# Neutrino-150.net
KiCad netlist of a schematic drawn in EAGLE
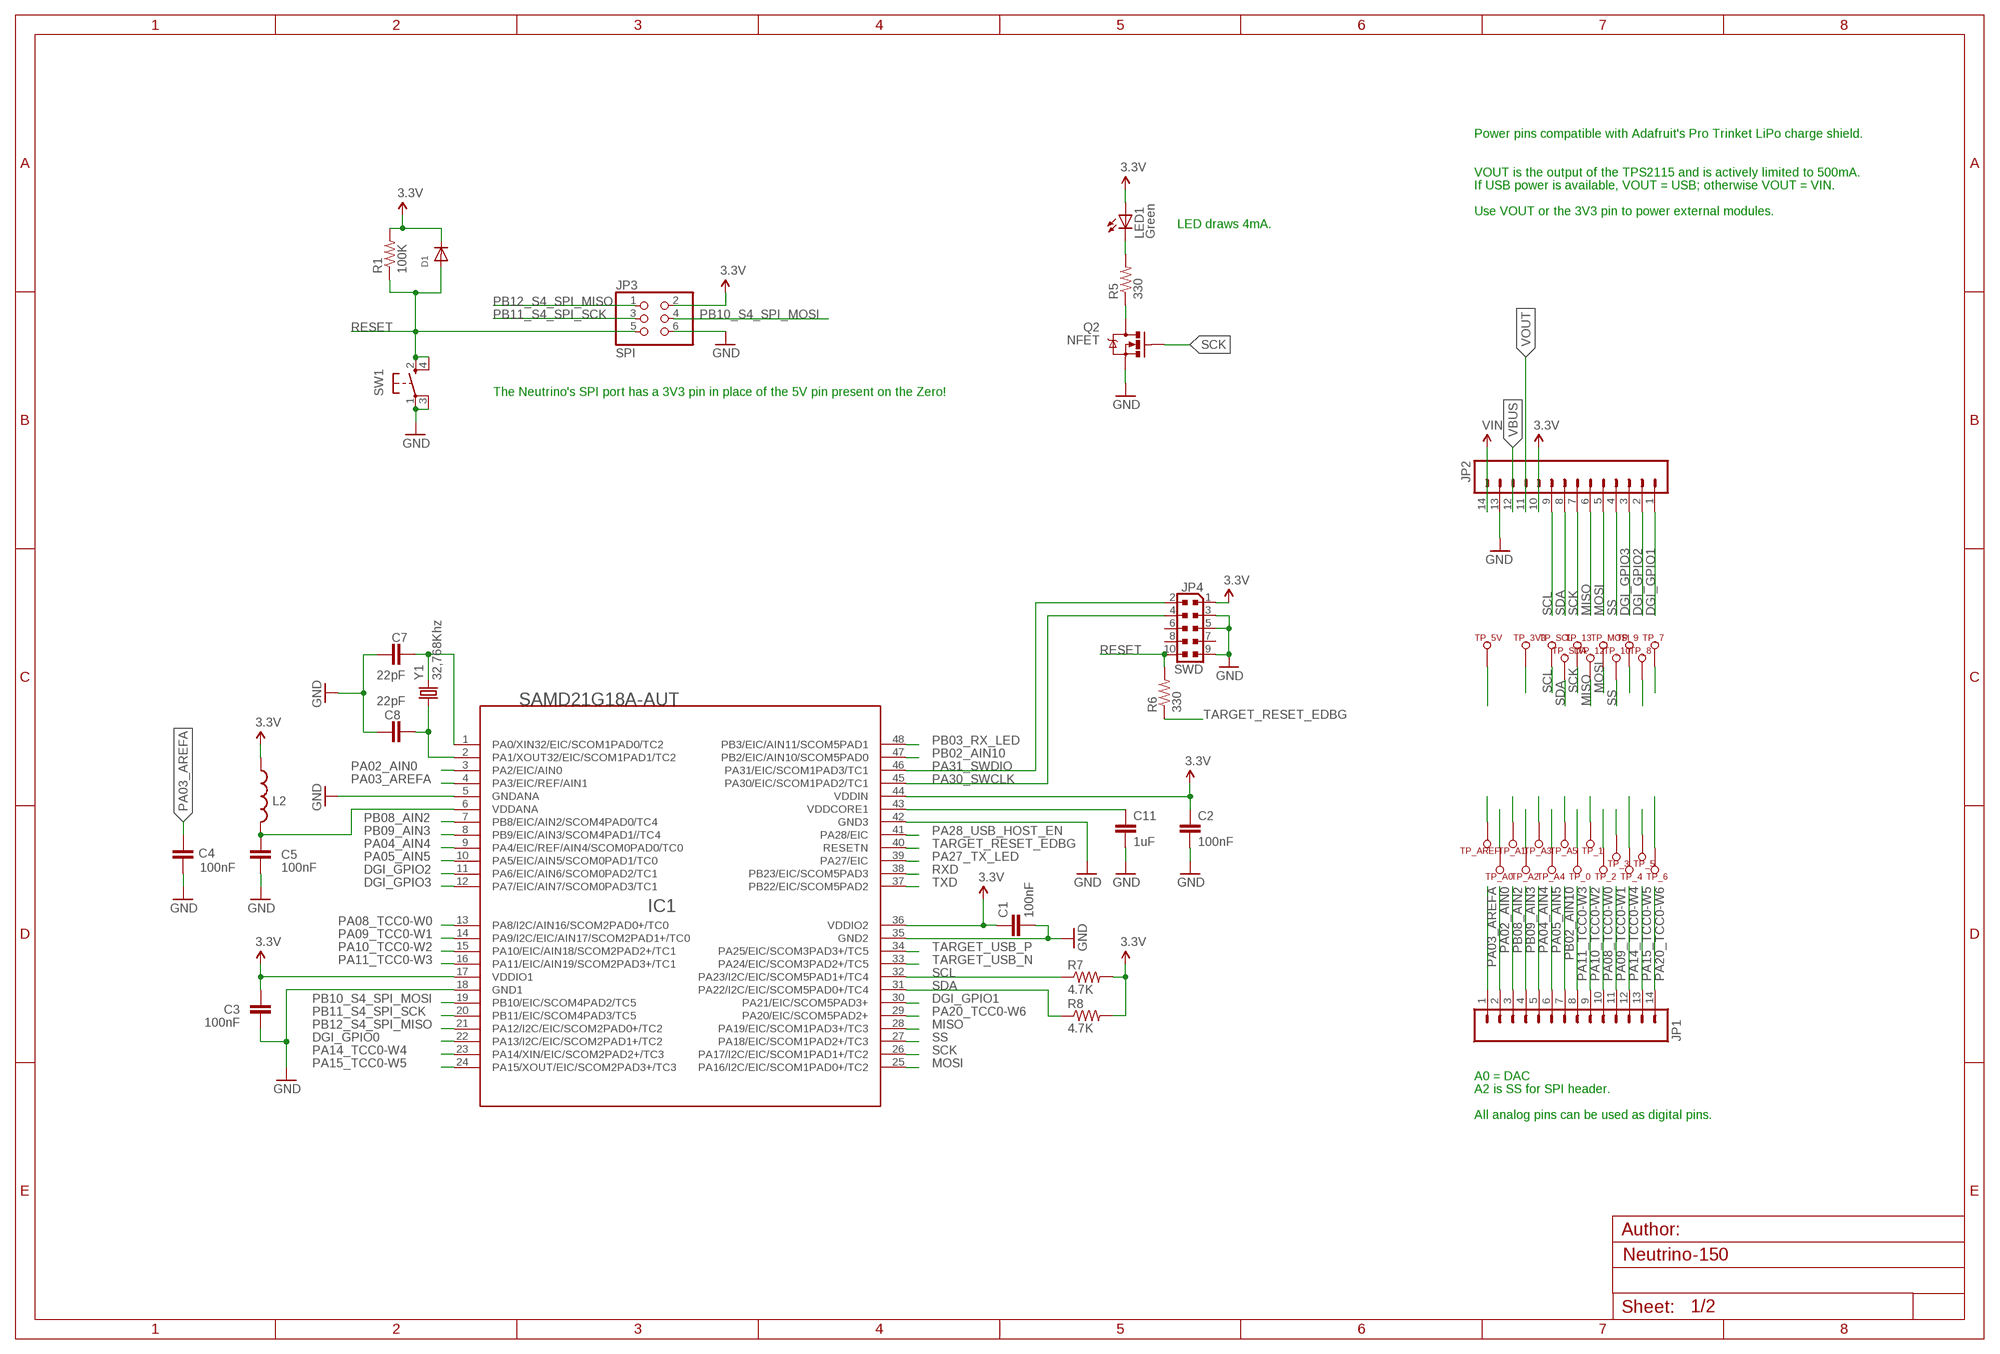
[diagram p0: schematic, sheet 1]
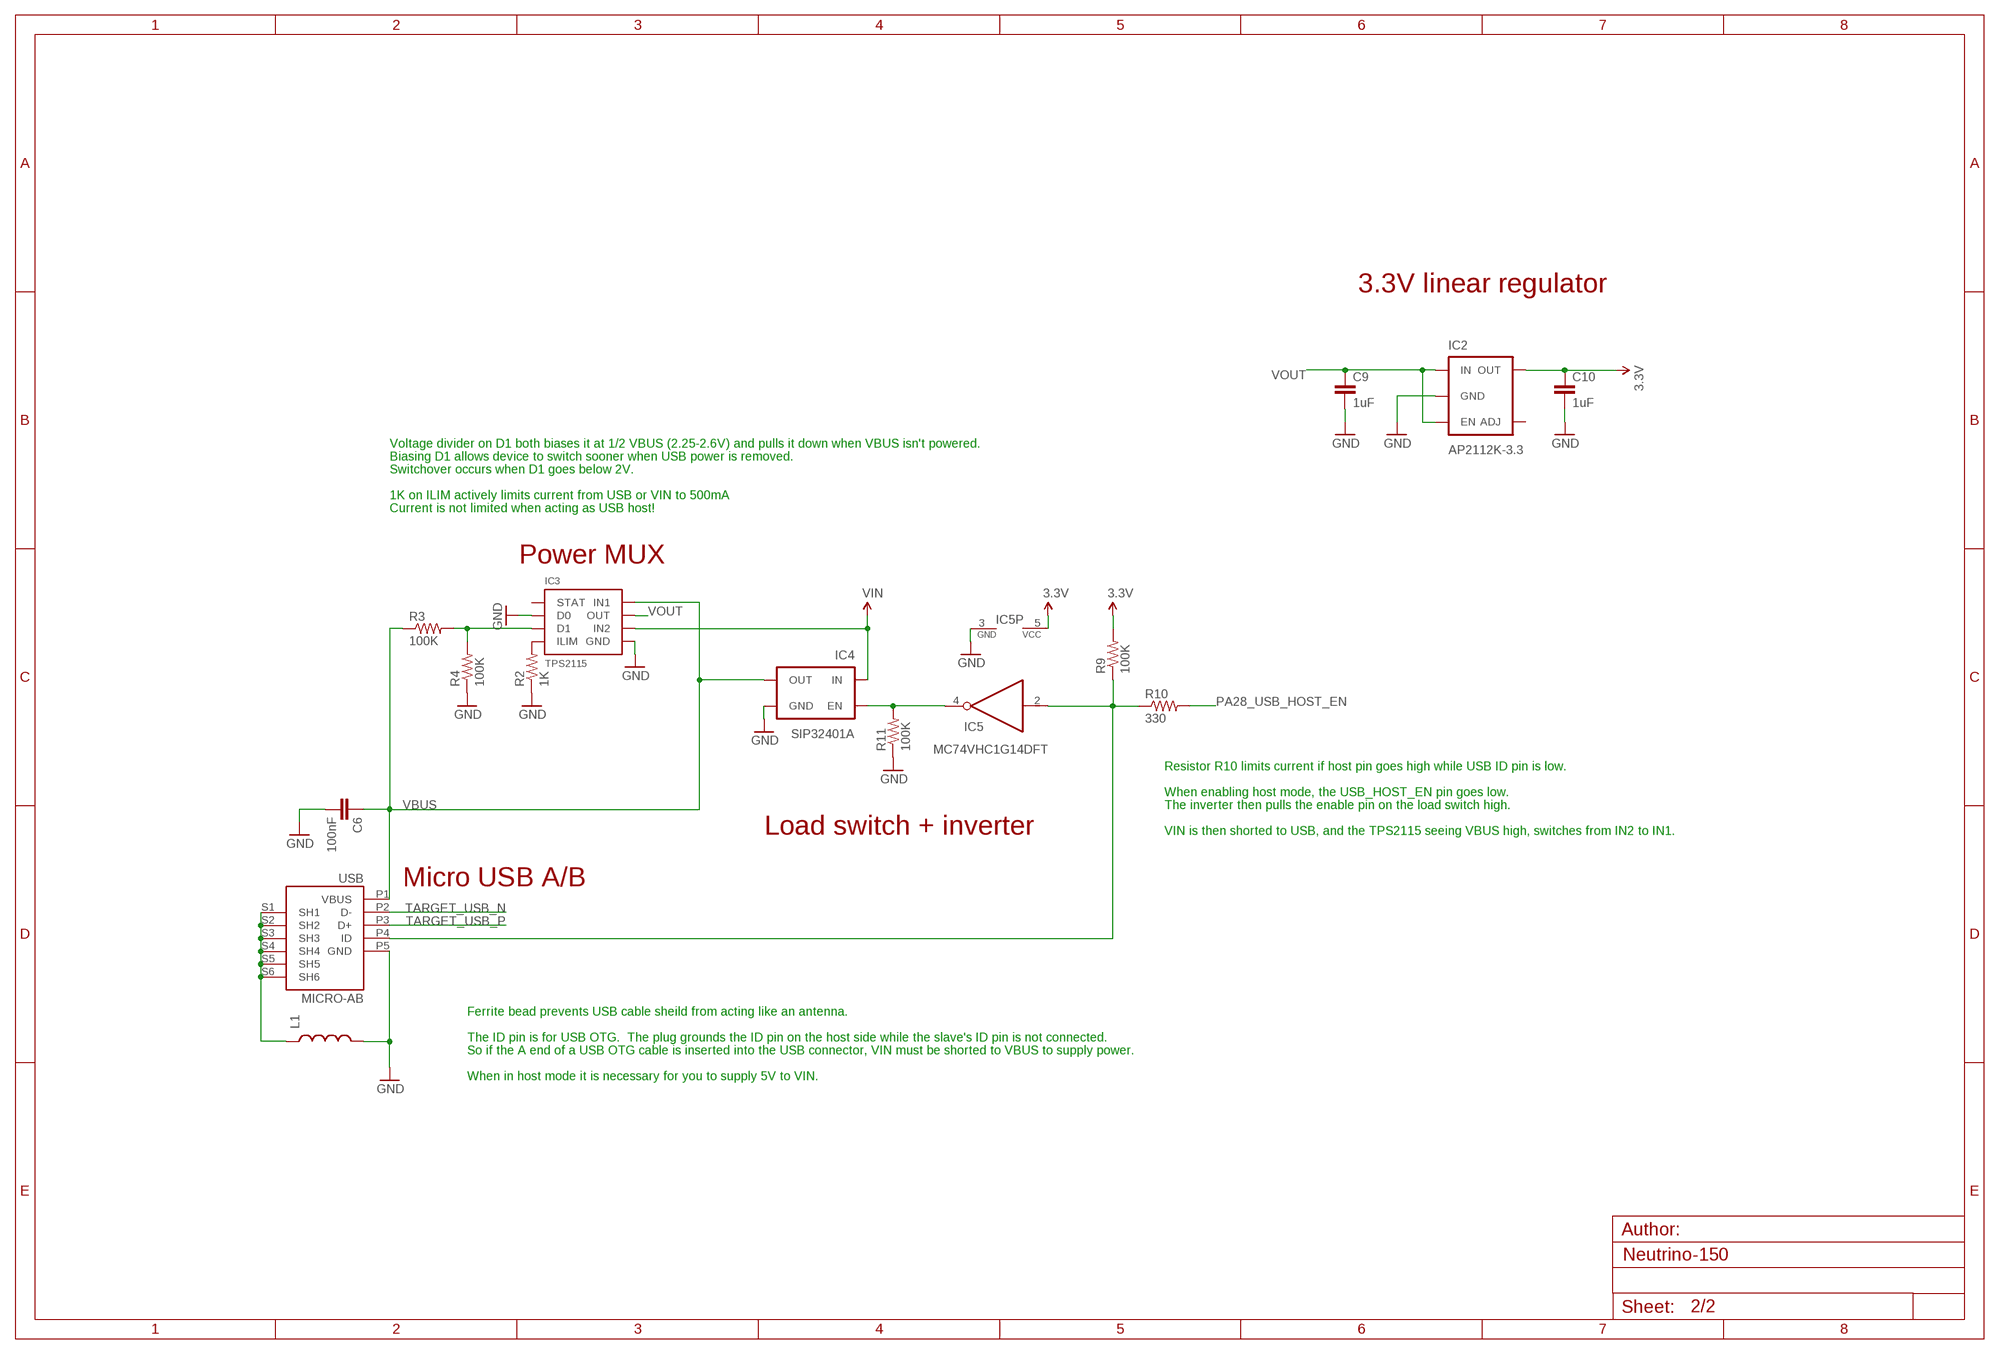
[diagram p1: schematic, sheet 2]

(export (version "E")
  (design (tool "Eeschema 10.0.6"))
  (components
    (comp (ref "C6")
      (value "100nF")
      (footprint "eagle-import:0402-CAP")
      (libsource (lib "eagle-import") (part "CAP0402"))
    )
    (comp (ref "C9")
      (value "1uF")
      (footprint "eagle-import:0402-CAP")
      (libsource (lib "eagle-import") (part "CAP0402"))
    )
    (comp (ref "C10")
      (value "1uF")
      (footprint "eagle-import:0402-CAP")
      (libsource (lib "eagle-import") (part "CAP0402"))
    )
    (comp (ref "IC2")
      (value "AP2112K-3.3")
      (footprint "eagle-import:SOT23-5")
      (libsource (lib "eagle-import") (part "AP2202-ADJ"))
    )
    (comp (ref "IC3")
      (value "TPS2115")
      (footprint "eagle-import:8-VDFN")
      (libsource (lib "eagle-import") (part "TPS2115"))
    )
    (comp (ref "IC4")
      (value "SIP32401A")
      (footprint "eagle-import:TDFN4")
      (libsource (lib "eagle-import") (part "SIP32401A"))
    )
    (comp (ref "IC5")
      (value "MC74VHC1G14DFT")
      (footprint "eagle-import:SC70-5")
      (libsource (lib "eagle-import") (part "741G04DCKAHC"))
    )
    (comp (ref "L1")
      (value "INDUCTOR0603-TDK")
      (footprint "eagle-import:0603-TDK")
      (libsource (lib "eagle-import") (part "INDUCTOR0603-TDK"))
    )
    (comp (ref "R2")
      (value "1K")
      (footprint "eagle-import:R0402-VISHAY")
      (libsource (lib "eagle-import") (part "R-US_R0402-VISHAY"))
    )
    (comp (ref "R3")
      (value "100K")
      (footprint "eagle-import:R0402-VISHAY")
      (libsource (lib "eagle-import") (part "R-US_R0402-VISHAY"))
    )
    (comp (ref "R4")
      (value "100K")
      (footprint "eagle-import:R0402-VISHAY")
      (libsource (lib "eagle-import") (part "R-US_R0402-VISHAY"))
    )
    (comp (ref "R9")
      (value "100K")
      (footprint "eagle-import:R0402-VISHAY")
      (libsource (lib "eagle-import") (part "R-US_R0402-VISHAY"))
    )
    (comp (ref "R10")
      (value "330")
      (footprint "eagle-import:R0402-VISHAY")
      (libsource (lib "eagle-import") (part "R-US_R0402-VISHAY"))
    )
    (comp (ref "R11")
      (value "100K")
      (footprint "eagle-import:R0402-VISHAY")
      (libsource (lib "eagle-import") (part "R-US_R0402-VISHAY"))
    )
    (comp (ref "USB")
      (value "MICRO-AB")
      (footprint "eagle-import:MOLEX_USB_MICRO_AB")
      (libsource (lib "eagle-import") (part "MOLEX_USB_MICRO_AB"))
    )
    (comp (ref "C1")
      (value "100nF")
      (footprint "eagle-import:0402-CAP")
      (libsource (lib "eagle-import") (part "CAP0402"))
    )
    (comp (ref "C2")
      (value "100nF")
      (footprint "eagle-import:0402-CAP")
      (libsource (lib "eagle-import") (part "CAP0402"))
    )
    (comp (ref "C3")
      (value "100nF")
      (footprint "eagle-import:0402-CAP")
      (libsource (lib "eagle-import") (part "CAP0402"))
    )
    (comp (ref "C4")
      (value "100nF")
      (footprint "eagle-import:0402-CAP")
      (libsource (lib "eagle-import") (part "CAP0402"))
    )
    (comp (ref "C5")
      (value "100nF")
      (footprint "eagle-import:0402-CAP")
      (libsource (lib "eagle-import") (part "CAP0402"))
    )
    (comp (ref "C7")
      (value "22pF")
      (footprint "eagle-import:0402-CAP")
      (libsource (lib "eagle-import") (part "CAP0402"))
    )
    (comp (ref "C8")
      (value "22pF")
      (footprint "eagle-import:0402-CAP")
      (libsource (lib "eagle-import") (part "CAP0402"))
    )
    (comp (ref "C11")
      (value "1uF")
      (footprint "eagle-import:0402-CAP")
      (libsource (lib "eagle-import") (part "CAP0402"))
    )
    (comp (ref "D1")
      (value "DIODESOD-523")
      (footprint "eagle-import:SOD-523")
      (libsource (lib "eagle-import") (part "DIODESOD-523"))
    )
    (comp (ref "IC1")
      (value "SAMD21G18A-AUT")
      (footprint "eagle-import:INTEGRATEDCIRCUITS_TQFP48-7X7")
      (libsource (lib "eagle-import") (part "INTEGRATEDCIRCUITS_1792_SAMD21G18A-AUT"))
    )
    (comp (ref "JP1")
      (value "M14NOSILK_SMALLPADS")
      (footprint "eagle-import:1X14_NO_SILK_SMALLPADS")
      (libsource (lib "eagle-import") (part "M14NOSILK_SMALLPADS"))
    )
    (comp (ref "JP2")
      (value "M14NOSILK_SMALLPADS")
      (footprint "eagle-import:1X14_NO_SILK_SMALLPADS")
      (libsource (lib "eagle-import") (part "M14NOSILK_SMALLPADS"))
    )
    (comp (ref "JP3")
      (value "SPI")
      (footprint "eagle-import:CONNETTORI_2X03")
      (fields (field (name "PART_NUMBER") "PH254-203DF118A00V"))
      (libsource (lib "eagle-import") (part "CONNETTORI_0114_PH254-203DF118A00V"))
    )
    (comp (ref "JP4")
      (value "SWD")
      (footprint "eagle-import:CONNETTORI_PINHEAD-2X5-P127")
      (libsource (lib "eagle-import") (part "CONNETTORI_0171_PH127-205DF055G00A"))
    )
    (comp (ref "L2")
      (value "INDUCTOR0603-TDK")
      (footprint "eagle-import:0603-TDK")
      (libsource (lib "eagle-import") (part "INDUCTOR0603-TDK"))
    )
    (comp (ref "LED1")
      (value "Green")
      (footprint "eagle-import:CHIPLED_0805")
      (fields (field (name "PART_NUMBER") "KPT-2012YC"))
      (libsource (lib "eagle-import") (part "0044_KPT-2012YC"))
    )
    (comp (ref "Q2")
      (value "NFET")
      (footprint "eagle-import:SOT323")
      (libsource (lib "eagle-import") (part "MOSFET-NCHANNEL2N7002PW"))
    )
    (comp (ref "R1")
      (value "100K")
      (footprint "eagle-import:R0402-VISHAY")
      (libsource (lib "eagle-import") (part "R-US_R0402-VISHAY"))
    )
    (comp (ref "R5")
      (value "330")
      (footprint "eagle-import:R0402-VISHAY")
      (libsource (lib "eagle-import") (part "R-US_R0402-VISHAY"))
    )
    (comp (ref "R6")
      (value "330")
      (footprint "eagle-import:R0402-VISHAY")
      (libsource (lib "eagle-import") (part "R-US_R0402-VISHAY"))
    )
    (comp (ref "R7")
      (value "4.7K")
      (footprint "eagle-import:R0402-VISHAY")
      (libsource (lib "eagle-import") (part "R-US_R0402-VISHAY"))
    )
    (comp (ref "R8")
      (value "4.7K")
      (footprint "eagle-import:R0402-VISHAY")
      (libsource (lib "eagle-import") (part "R-US_R0402-VISHAY"))
    )
    (comp (ref "SW1")
      (value "SPST_TACT-KMR2")
      (footprint "eagle-import:KMR2")
      (libsource (lib "eagle-import") (part "SPST_TACT-KMR2"))
    )
    (comp (ref "TP_0")
      (value "TP_SP")
      (footprint "eagle-import:TP-SP")
      (libsource (lib "eagle-import") (part "TP_SP"))
    )
    (comp (ref "TP_1")
      (value "TP_SP")
      (footprint "eagle-import:TP-SP")
      (libsource (lib "eagle-import") (part "TP_SP"))
    )
    (comp (ref "TP_2")
      (value "TP_SP")
      (footprint "eagle-import:TP-SP")
      (libsource (lib "eagle-import") (part "TP_SP"))
    )
    (comp (ref "TP_3")
      (value "TP_SP")
      (footprint "eagle-import:TP-SP")
      (libsource (lib "eagle-import") (part "TP_SP"))
    )
    (comp (ref "TP_3V3")
      (value "TP_SP")
      (footprint "eagle-import:TP-SP")
      (libsource (lib "eagle-import") (part "TP_SP"))
    )
    (comp (ref "TP_4")
      (value "TP_SP")
      (footprint "eagle-import:TP-SP")
      (libsource (lib "eagle-import") (part "TP_SP"))
    )
    (comp (ref "TP_5")
      (value "TP_SP")
      (footprint "eagle-import:TP-SP")
      (libsource (lib "eagle-import") (part "TP_SP"))
    )
    (comp (ref "TP_5V")
      (value "TP_SP")
      (footprint "eagle-import:TP-SP")
      (libsource (lib "eagle-import") (part "TP_SP"))
    )
    (comp (ref "TP_6")
      (value "TP_SP")
      (footprint "eagle-import:TP-SP")
      (libsource (lib "eagle-import") (part "TP_SP"))
    )
    (comp (ref "TP_7")
      (value "TP_SP")
      (footprint "eagle-import:TP-SP")
      (libsource (lib "eagle-import") (part "TP_SP"))
    )
    (comp (ref "TP_8")
      (value "TP_SP")
      (footprint "eagle-import:TP-SP")
      (libsource (lib "eagle-import") (part "TP_SP"))
    )
    (comp (ref "TP_9")
      (value "TP_SP")
      (footprint "eagle-import:TP-SP")
      (libsource (lib "eagle-import") (part "TP_SP"))
    )
    (comp (ref "TP_10")
      (value "TP_SP")
      (footprint "eagle-import:TP-SP")
      (libsource (lib "eagle-import") (part "TP_SP"))
    )
    (comp (ref "TP_12")
      (value "TP_SP")
      (footprint "eagle-import:TP-SP")
      (libsource (lib "eagle-import") (part "TP_SP"))
    )
    (comp (ref "TP_13")
      (value "TP_SP")
      (footprint "eagle-import:TP-SP")
      (libsource (lib "eagle-import") (part "TP_SP"))
    )
    (comp (ref "TP_A0")
      (value "TP_SP")
      (footprint "eagle-import:TP-SP")
      (libsource (lib "eagle-import") (part "TP_SP"))
    )
    (comp (ref "TP_A1")
      (value "TP_SP")
      (footprint "eagle-import:TP-SP")
      (libsource (lib "eagle-import") (part "TP_SP"))
    )
    (comp (ref "TP_A2")
      (value "TP_SP")
      (footprint "eagle-import:TP-SP")
      (libsource (lib "eagle-import") (part "TP_SP"))
    )
    (comp (ref "TP_A3")
      (value "TP_SP")
      (footprint "eagle-import:TP-SP")
      (libsource (lib "eagle-import") (part "TP_SP"))
    )
    (comp (ref "TP_A4")
      (value "TP_SP")
      (footprint "eagle-import:TP-SP")
      (libsource (lib "eagle-import") (part "TP_SP"))
    )
    (comp (ref "TP_A5")
      (value "TP_SP")
      (footprint "eagle-import:TP-SP")
      (libsource (lib "eagle-import") (part "TP_SP"))
    )
    (comp (ref "TP_AREF")
      (value "TP_SP")
      (footprint "eagle-import:TP-SP")
      (libsource (lib "eagle-import") (part "TP_SP"))
    )
    (comp (ref "TP_MOSI")
      (value "TP_SP")
      (footprint "eagle-import:TP-SP")
      (libsource (lib "eagle-import") (part "TP_SP"))
    )
    (comp (ref "TP_SCL")
      (value "TP_SP")
      (footprint "eagle-import:TP-SP")
      (libsource (lib "eagle-import") (part "TP_SP"))
    )
    (comp (ref "TP_SDA")
      (value "TP_SP")
      (footprint "eagle-import:TP-SP")
      (libsource (lib "eagle-import") (part "TP_SP"))
    )
    (comp (ref "Y1")
      (value "32,768Khz")
      (footprint "eagle-import:CRYSTAL-SMD-2.0X1.2")
      (libsource (lib "eagle-import") (part "CRYSTAL2012"))
    )
  )
  (nets
    (net (code "1") (name "3.3V") (class "Default")
      (node (ref "C1") (pin "1") (pinfunction "1_1") (pintype "passive"))
      (node (ref "C10") (pin "1") (pinfunction "1_1") (pintype "passive"))
      (node (ref "C2") (pin "1") (pinfunction "1_1") (pintype "passive"))
      (node (ref "C3") (pin "2") (pinfunction "2_2") (pintype "passive"))
      (node (ref "D1") (pin "K") (pinfunction "C_K") (pintype "passive"))
      (node (ref "IC1") (pin "17") (pinfunction "VDDIO1_17") (pintype "power_in"))
      (node (ref "IC1") (pin "36") (pinfunction "VDDIO2_36") (pintype "power_in"))
      (node (ref "IC1") (pin "44") (pinfunction "VDDIN_44") (pintype "power_in"))
      (node (ref "IC2") (pin "5") (pinfunction "OUT_5") (pintype "passive"))
      (node (ref "IC5") (pin "5") (pinfunction "VCC_5") (pintype "power_in"))
      (node (ref "JP2") (pin "10") (pinfunction "10_10") (pintype "passive"))
      (node (ref "JP3") (pin "2") (pinfunction "2_2") (pintype "passive"))
      (node (ref "JP4") (pin "1") (pinfunction "1_1") (pintype "passive"))
      (node (ref "L2") (pin "1") (pinfunction "1_1") (pintype "passive"))
      (node (ref "LED1") (pin "A") (pinfunction "A_A") (pintype "passive"))
      (node (ref "R1") (pin "2") (pinfunction "2_2") (pintype "passive"))
      (node (ref "R7") (pin "2") (pinfunction "2_2") (pintype "passive"))
      (node (ref "R8") (pin "2") (pinfunction "2_2") (pintype "passive"))
      (node (ref "R9") (pin "2") (pinfunction "2_2") (pintype "passive"))
      (node (ref "TP_3V3") (pin "X") (pinfunction "TESTP_X") (pintype "passive"))
    )
    (net (code "2") (name "DGI_GPIO0") (class "Default")
      (node (ref "IC1") (pin "22") (pinfunction "PA13/I2C/EIC/SCOM2PAD1+/TC2_22") (pintype "bidirectional"))
    )
    (net (code "3") (name "DGI_GPIO1") (class "Default")
      (node (ref "IC1") (pin "30") (pinfunction "PA21/EIC/SCOM5PAD3+_30") (pintype "bidirectional"))
      (node (ref "JP2") (pin "1") (pinfunction "1_1") (pintype "passive"))
      (node (ref "TP_7") (pin "X") (pinfunction "TESTP_X") (pintype "passive"))
    )
    (net (code "4") (name "DGI_GPIO2") (class "Default")
      (node (ref "IC1") (pin "11") (pinfunction "PA6/EIC/AIN6/SCOM0PAD2/TC1_11") (pintype "bidirectional"))
      (node (ref "JP2") (pin "2") (pinfunction "2_2") (pintype "passive"))
      (node (ref "TP_8") (pin "X") (pinfunction "TESTP_X") (pintype "passive"))
    )
    (net (code "5") (name "DGI_GPIO3") (class "Default")
      (node (ref "IC1") (pin "12") (pinfunction "PA7/EIC/AIN7/SCOM0PAD3/TC1_12") (pintype "bidirectional"))
      (node (ref "JP2") (pin "3") (pinfunction "3_3") (pintype "passive"))
      (node (ref "TP_9") (pin "X") (pinfunction "TESTP_X") (pintype "passive"))
    )
    (net (code "6") (name "GND") (class "Default")
      (node (ref "C1") (pin "2") (pinfunction "2_2") (pintype "passive"))
      (node (ref "C10") (pin "2") (pinfunction "2_2") (pintype "passive"))
      (node (ref "C11") (pin "2") (pinfunction "2_2") (pintype "passive"))
      (node (ref "C2") (pin "2") (pinfunction "2_2") (pintype "passive"))
      (node (ref "C3") (pin "1") (pinfunction "1_1") (pintype "passive"))
      (node (ref "C4") (pin "2") (pinfunction "2_2") (pintype "passive"))
      (node (ref "C5") (pin "2") (pinfunction "2_2") (pintype "passive"))
      (node (ref "C6") (pin "2") (pinfunction "2_2") (pintype "passive"))
      (node (ref "C7") (pin "1") (pinfunction "1_1") (pintype "passive"))
      (node (ref "C8") (pin "1") (pinfunction "1_1") (pintype "passive"))
      (node (ref "C9") (pin "2") (pinfunction "2_2") (pintype "passive"))
      (node (ref "IC1") (pin "18") (pinfunction "GND1_18") (pintype "power_in"))
      (node (ref "IC1") (pin "35") (pinfunction "GND2_35") (pintype "power_in"))
      (node (ref "IC1") (pin "42") (pinfunction "GND3_42") (pintype "power_in"))
      (node (ref "IC1") (pin "5") (pinfunction "GNDANA_5") (pintype "power_in"))
      (node (ref "IC2") (pin "2") (pinfunction "GND_2") (pintype "input"))
      (node (ref "IC3") (pin "2") (pinfunction "D0_2") (pintype "bidirectional"))
      (node (ref "IC3") (pin "5") (pinfunction "GND_5") (pintype "bidirectional"))
      (node (ref "IC3") (pin "P0") (pinfunction "GND_P0") (pintype "bidirectional"))
      (node (ref "IC3") (pin "V0") (pinfunction "GND_V0") (pintype "bidirectional"))
      (node (ref "IC3") (pin "V1") (pinfunction "GND_V1") (pintype "bidirectional"))
      (node (ref "IC3") (pin "V2") (pinfunction "GND_V2") (pintype "bidirectional"))
      (node (ref "IC3") (pin "V3") (pinfunction "GND_V3") (pintype "bidirectional"))
      (node (ref "IC3") (pin "V4") (pinfunction "GND_V4") (pintype "bidirectional"))
      (node (ref "IC4") (pin "0") (pinfunction "GND_0") (pintype "power_in"))
      (node (ref "IC4") (pin "2") (pinfunction "GND_2") (pintype "power_in"))
      (node (ref "IC5") (pin "3") (pinfunction "GND_3") (pintype "power_in"))
      (node (ref "JP2") (pin "13") (pinfunction "13_13") (pintype "passive"))
      (node (ref "JP3") (pin "6") (pinfunction "6_6") (pintype "passive"))
      (node (ref "JP4") (pin "3") (pinfunction "3_3") (pintype "passive"))
      (node (ref "JP4") (pin "5") (pinfunction "5_5") (pintype "passive"))
      (node (ref "JP4") (pin "9") (pinfunction "9_9") (pintype "passive"))
      (node (ref "L1") (pin "2") (pinfunction "2_2") (pintype "passive"))
      (node (ref "Q2") (pin "2") (pinfunction "S_2") (pintype "passive"))
      (node (ref "R11") (pin "1") (pinfunction "1_1") (pintype "passive"))
      (node (ref "R2") (pin "1") (pinfunction "1_1") (pintype "passive"))
      (node (ref "R4") (pin "1") (pinfunction "1_1") (pintype "passive"))
      (node (ref "SW1") (pin "1") (pinfunction "P_1") (pintype "passive"))
      (node (ref "SW1") (pin "3") (pinfunction "P1_3") (pintype "passive"))
      (node (ref "USB") (pin "P5") (pinfunction "GND_P5") (pintype "passive"))
    )
    (net (code "7") (name "MISO") (class "Default")
      (node (ref "IC1") (pin "28") (pinfunction "PA19/EIC/SCOM1PAD3+/TC3_28") (pintype "bidirectional"))
      (node (ref "JP2") (pin "6") (pinfunction "6_6") (pintype "passive"))
      (node (ref "TP_12") (pin "X") (pinfunction "TESTP_X") (pintype "passive"))
    )
    (net (code "8") (name "MOSI") (class "Default")
      (node (ref "IC1") (pin "25") (pinfunction "PA16/I2C/EIC/SCOM1PAD0+/TC2_25") (pintype "bidirectional"))
      (node (ref "JP2") (pin "5") (pinfunction "5_5") (pintype "passive"))
      (node (ref "TP_MOSI") (pin "X") (pinfunction "TESTP_X") (pintype "passive"))
    )
    (net (code "9") (name "Net-(IC1-PA0{slash}XIN32{slash}EIC{slash}SCOM1PAD0{slash}TC2)") (class "Default")
      (node (ref "C7") (pin "2") (pinfunction "2_2") (pintype "passive"))
      (node (ref "IC1") (pin "1") (pinfunction "PA0/XIN32/EIC/SCOM1PAD0/TC2_1") (pintype "bidirectional"))
      (node (ref "Y1") (pin "2") (pinfunction "2_2") (pintype "passive"))
    )
    (net (code "10") (name "Net-(IC1-PA1{slash}XOUT32{slash}EIC{slash}SCOM1PAD1{slash}TC2)") (class "Default")
      (node (ref "C8") (pin "2") (pinfunction "2_2") (pintype "passive"))
      (node (ref "IC1") (pin "2") (pinfunction "PA1/XOUT32/EIC/SCOM1PAD1/TC2_2") (pintype "bidirectional"))
      (node (ref "Y1") (pin "1") (pinfunction "1_1") (pintype "passive"))
    )
    (net (code "11") (name "Net-(IC1-VDDANA)") (class "Default")
      (node (ref "C5") (pin "1") (pinfunction "1_1") (pintype "passive"))
      (node (ref "IC1") (pin "6") (pinfunction "VDDANA_6") (pintype "power_in"))
      (node (ref "L2") (pin "2") (pinfunction "2_2") (pintype "passive"))
    )
    (net (code "12") (name "Net-(IC1-VDDCORE1)") (class "Default")
      (node (ref "C11") (pin "1") (pinfunction "1_1") (pintype "passive"))
      (node (ref "IC1") (pin "43") (pinfunction "VDDCORE1_43") (pintype "input"))
    )
    (net (code "13") (name "Net-(IC3-D1)") (class "Default")
      (node (ref "IC3") (pin "3") (pinfunction "D1_3") (pintype "bidirectional"))
      (node (ref "R3") (pin "2") (pinfunction "2_2") (pintype "passive"))
      (node (ref "R4") (pin "2") (pinfunction "2_2") (pintype "passive"))
    )
    (net (code "14") (name "Net-(IC3-ILIM)") (class "Default")
      (node (ref "IC3") (pin "4") (pinfunction "ILIM_4") (pintype "bidirectional"))
      (node (ref "R2") (pin "2") (pinfunction "2_2") (pintype "passive"))
    )
    (net (code "15") (name "Net-(IC4-EN)") (class "Default")
      (node (ref "IC4") (pin "4") (pinfunction "EN_4") (pintype "input"))
      (node (ref "IC5") (pin "4") (pinfunction "O_4") (pintype "output"))
      (node (ref "R11") (pin "2") (pinfunction "2_2") (pintype "passive"))
    )
    (net (code "16") (name "Net-(IC5A-I)") (class "Default")
      (node (ref "IC5") (pin "2") (pinfunction "I_2") (pintype "input"))
      (node (ref "R10") (pin "1") (pinfunction "1_1") (pintype "passive"))
      (node (ref "R9") (pin "1") (pinfunction "1_1") (pintype "passive"))
      (node (ref "USB") (pin "P4") (pinfunction "ID_P4") (pintype "bidirectional"))
    )
    (net (code "17") (name "Net-(LED1-PadC)") (class "Default")
      (node (ref "LED1") (pin "C") (pinfunction "C_C") (pintype "passive"))
      (node (ref "R5") (pin "2") (pinfunction "2_2") (pintype "passive"))
    )
    (net (code "18") (name "Net-(Q2-D)") (class "Default")
      (node (ref "Q2") (pin "3") (pinfunction "D_3") (pintype "passive"))
      (node (ref "R5") (pin "1") (pinfunction "1_1") (pintype "passive"))
    )
    (net (code "19") (name "Net-(USB-SH1)") (class "Default")
      (node (ref "L1") (pin "1") (pinfunction "1_1") (pintype "passive"))
      (node (ref "USB") (pin "S1") (pinfunction "SH1_S1") (pintype "passive"))
      (node (ref "USB") (pin "S2") (pinfunction "SH2_S2") (pintype "passive"))
      (node (ref "USB") (pin "S3") (pinfunction "SH3_S3") (pintype "passive"))
      (node (ref "USB") (pin "S4") (pinfunction "SH4_S4") (pintype "passive"))
      (node (ref "USB") (pin "S5") (pinfunction "SH5_S5") (pintype "passive"))
      (node (ref "USB") (pin "S6") (pinfunction "SH6_S6") (pintype "passive"))
    )
    (net (code "20") (name "PA02_AIN0") (class "Default")
      (node (ref "IC1") (pin "3") (pinfunction "PA2/EIC/AIN0_3") (pintype "bidirectional"))
      (node (ref "JP1") (pin "2") (pinfunction "2_2") (pintype "passive"))
      (node (ref "TP_A0") (pin "X") (pinfunction "TESTP_X") (pintype "passive"))
    )
    (net (code "21") (name "PA03_AREFA") (class "Default")
      (node (ref "C4") (pin "1") (pinfunction "1_1") (pintype "passive"))
      (node (ref "IC1") (pin "4") (pinfunction "PA3/EIC/REF/AIN1_4") (pintype "bidirectional"))
      (node (ref "JP1") (pin "1") (pinfunction "1_1") (pintype "passive"))
      (node (ref "TP_AREF") (pin "X") (pinfunction "TESTP_X") (pintype "passive"))
    )
    (net (code "22") (name "PA04_AIN4") (class "Default")
      (node (ref "IC1") (pin "9") (pinfunction "PA4/EIC/REF/AIN4/SCOM0PAD0/TC0_9") (pintype "bidirectional"))
      (node (ref "JP1") (pin "5") (pinfunction "5_5") (pintype "passive"))
      (node (ref "TP_A3") (pin "X") (pinfunction "TESTP_X") (pintype "passive"))
    )
    (net (code "23") (name "PA05_AIN5") (class "Default")
      (node (ref "IC1") (pin "10") (pinfunction "PA5/EIC/AIN5/SCOM0PAD1/TC0_10") (pintype "bidirectional"))
      (node (ref "JP1") (pin "6") (pinfunction "6_6") (pintype "passive"))
      (node (ref "TP_A4") (pin "X") (pinfunction "TESTP_X") (pintype "passive"))
    )
    (net (code "24") (name "PA08_TCC0-W0") (class "Default")
      (node (ref "IC1") (pin "13") (pinfunction "PA8/I2C/AIN16/SCOM2PAD0+/TC0_13") (pintype "bidirectional"))
      (node (ref "JP1") (pin "10") (pinfunction "10_10") (pintype "passive"))
      (node (ref "TP_2") (pin "X") (pinfunction "TESTP_X") (pintype "passive"))
    )
    (net (code "25") (name "PA09_TCC0-W1") (class "Default")
      (node (ref "IC1") (pin "14") (pinfunction "PA9/I2C/EIC/AIN17/SCOM2PAD1+/TC0_14") (pintype "bidirectional"))
      (node (ref "JP1") (pin "11") (pinfunction "11_11") (pintype "passive"))
      (node (ref "TP_3") (pin "X") (pinfunction "TESTP_X") (pintype "passive"))
    )
    (net (code "26") (name "PA10_TCC0-W2") (class "Default")
      (node (ref "IC1") (pin "15") (pinfunction "PA10/EIC/AIN18/SCOM2PAD2+/TC1_15") (pintype "bidirectional"))
      (node (ref "JP1") (pin "9") (pinfunction "9_9") (pintype "passive"))
      (node (ref "TP_1") (pin "X") (pinfunction "TESTP_X") (pintype "passive"))
    )
    (net (code "27") (name "PA11_TCC0-W3") (class "Default")
      (node (ref "IC1") (pin "16") (pinfunction "PA11/EIC/AIN19/SCOM2PAD3+/TC1_16") (pintype "bidirectional"))
      (node (ref "JP1") (pin "8") (pinfunction "8_8") (pintype "passive"))
      (node (ref "TP_0") (pin "X") (pinfunction "TESTP_X") (pintype "passive"))
    )
    (net (code "28") (name "PA14_TCC0-W4") (class "Default")
      (node (ref "IC1") (pin "23") (pinfunction "PA14/XIN/EIC/SCOM2PAD2+/TC3_23") (pintype "bidirectional"))
      (node (ref "JP1") (pin "12") (pinfunction "12_12") (pintype "passive"))
      (node (ref "TP_4") (pin "X") (pinfunction "TESTP_X") (pintype "passive"))
    )
    (net (code "29") (name "PA15_TCC0-W5") (class "Default")
      (node (ref "IC1") (pin "24") (pinfunction "PA15/XOUT/EIC/SCOM2PAD3+/TC3_24") (pintype "bidirectional"))
      (node (ref "JP1") (pin "13") (pinfunction "13_13") (pintype "passive"))
      (node (ref "TP_5") (pin "X") (pinfunction "TESTP_X") (pintype "passive"))
    )
    (net (code "30") (name "PA20_TCC0-W6") (class "Default")
      (node (ref "IC1") (pin "29") (pinfunction "PA20/EIC/SCOM5PAD2+_29") (pintype "bidirectional"))
      (node (ref "JP1") (pin "14") (pinfunction "14_14") (pintype "passive"))
      (node (ref "TP_6") (pin "X") (pinfunction "TESTP_X") (pintype "passive"))
    )
    (net (code "31") (name "PA27_TX_LED") (class "Default")
      (node (ref "IC1") (pin "39") (pinfunction "PA27/EIC_39") (pintype "bidirectional"))
    )
    (net (code "32") (name "PA28_USB_HOST_EN") (class "Default")
      (node (ref "IC1") (pin "41") (pinfunction "PA28/EIC_41") (pintype "bidirectional"))
      (node (ref "R10") (pin "2") (pinfunction "2_2") (pintype "passive"))
    )
    (net (code "33") (name "PA30_SWCLK") (class "Default")
      (node (ref "IC1") (pin "45") (pinfunction "PA30/EIC/SCOM1PAD2/TC1_45") (pintype "bidirectional"))
      (node (ref "JP4") (pin "4") (pinfunction "4_4") (pintype "passive"))
    )
    (net (code "34") (name "PA31_SWDIO") (class "Default")
      (node (ref "IC1") (pin "46") (pinfunction "PA31/EIC/SCOM1PAD3/TC1_46") (pintype "bidirectional"))
      (node (ref "JP4") (pin "2") (pinfunction "2_2") (pintype "passive"))
    )
    (net (code "35") (name "PB02_AIN10") (class "Default")
      (node (ref "IC1") (pin "47") (pinfunction "PB2/EIC/AIN10/SCOM5PAD0_47") (pintype "bidirectional"))
      (node (ref "JP1") (pin "7") (pinfunction "7_7") (pintype "passive"))
      (node (ref "TP_A5") (pin "X") (pinfunction "TESTP_X") (pintype "passive"))
    )
    (net (code "36") (name "PB03_RX_LED") (class "Default")
      (node (ref "IC1") (pin "48") (pinfunction "PB3/EIC/AIN11/SCOM5PAD1_48") (pintype "bidirectional"))
    )
    (net (code "37") (name "PB08_AIN2") (class "Default")
      (node (ref "IC1") (pin "7") (pinfunction "PB8/EIC/AIN2/SCOM4PAD0/TC4_7") (pintype "bidirectional"))
      (node (ref "JP1") (pin "3") (pinfunction "3_3") (pintype "passive"))
      (node (ref "TP_A1") (pin "X") (pinfunction "TESTP_X") (pintype "passive"))
    )
    (net (code "38") (name "PB09_AIN3") (class "Default")
      (node (ref "IC1") (pin "8") (pinfunction "PB9/EIC/AIN3/SCOM4PAD1//TC4_8") (pintype "bidirectional"))
      (node (ref "JP1") (pin "4") (pinfunction "4_4") (pintype "passive"))
      (node (ref "TP_A2") (pin "X") (pinfunction "TESTP_X") (pintype "passive"))
    )
    (net (code "39") (name "PB10_S4_SPI_MOSI") (class "Default")
      (node (ref "IC1") (pin "19") (pinfunction "PB10/EIC/SCOM4PAD2/TC5_19") (pintype "bidirectional"))
      (node (ref "JP3") (pin "4") (pinfunction "4_4") (pintype "passive"))
    )
    (net (code "40") (name "PB11_S4_SPI_SCK") (class "Default")
      (node (ref "IC1") (pin "20") (pinfunction "PB11/EIC/SCOM4PAD3/TC5_20") (pintype "bidirectional"))
      (node (ref "JP3") (pin "3") (pinfunction "3_3") (pintype "passive"))
    )
    (net (code "41") (name "PB12_S4_SPI_MISO") (class "Default")
      (node (ref "IC1") (pin "21") (pinfunction "PA12/I2C/EIC/SCOM2PAD0+/TC2_21") (pintype "bidirectional"))
      (node (ref "JP3") (pin "1") (pinfunction "1_1") (pintype "passive"))
    )
    (net (code "42") (name "RESET") (class "Default")
      (node (ref "D1") (pin "A") (pinfunction "A_A") (pintype "passive"))
      (node (ref "JP3") (pin "5") (pinfunction "5_5") (pintype "passive"))
      (node (ref "JP4") (pin "10") (pinfunction "10_10") (pintype "passive"))
      (node (ref "R1") (pin "1") (pinfunction "1_1") (pintype "passive"))
      (node (ref "R6") (pin "2") (pinfunction "2_2") (pintype "passive"))
      (node (ref "SW1") (pin "2") (pinfunction "S_2") (pintype "passive"))
      (node (ref "SW1") (pin "4") (pinfunction "S1_4") (pintype "passive"))
    )
    (net (code "43") (name "RXD") (class "Default")
      (node (ref "IC1") (pin "38") (pinfunction "PB23/EIC/SCOM5PAD3_38") (pintype "bidirectional"))
    )
    (net (code "44") (name "SCK") (class "Default")
      (node (ref "IC1") (pin "26") (pinfunction "PA17/I2C/EIC/SCOM1PAD1+/TC2_26") (pintype "bidirectional"))
      (node (ref "JP2") (pin "7") (pinfunction "7_7") (pintype "passive"))
      (node (ref "Q2") (pin "1") (pinfunction "G_1") (pintype "passive"))
      (node (ref "TP_13") (pin "X") (pinfunction "TESTP_X") (pintype "passive"))
    )
    (net (code "45") (name "SCL") (class "Default")
      (node (ref "IC1") (pin "32") (pinfunction "PA23/I2C/EIC/SCOM5PAD1+/TC4_32") (pintype "bidirectional"))
      (node (ref "JP2") (pin "9") (pinfunction "9_9") (pintype "passive"))
      (node (ref "R7") (pin "1") (pinfunction "1_1") (pintype "passive"))
      (node (ref "TP_SCL") (pin "X") (pinfunction "TESTP_X") (pintype "passive"))
    )
    (net (code "46") (name "SDA") (class "Default")
      (node (ref "IC1") (pin "31") (pinfunction "PA22/I2C/EIC/SCOM5PAD0+/TC4_31") (pintype "bidirectional"))
      (node (ref "JP2") (pin "8") (pinfunction "8_8") (pintype "passive"))
      (node (ref "R8") (pin "1") (pinfunction "1_1") (pintype "passive"))
      (node (ref "TP_SDA") (pin "X") (pinfunction "TESTP_X") (pintype "passive"))
    )
    (net (code "47") (name "SS") (class "Default")
      (node (ref "IC1") (pin "27") (pinfunction "PA18/EIC/SCOM1PAD2+/TC3_27") (pintype "bidirectional"))
      (node (ref "JP2") (pin "4") (pinfunction "4_4") (pintype "passive"))
      (node (ref "TP_10") (pin "X") (pinfunction "TESTP_X") (pintype "passive"))
    )
    (net (code "48") (name "TARGET_RESET_EDBG") (class "Default")
      (node (ref "IC1") (pin "40") (pinfunction "RESETN_40") (pintype "bidirectional"))
      (node (ref "R6") (pin "1") (pinfunction "1_1") (pintype "passive"))
    )
    (net (code "49") (name "TARGET_USB_N") (class "Default")
      (node (ref "IC1") (pin "33") (pinfunction "PA24/EIC/SCOM3PAD2+/TC5_33") (pintype "bidirectional"))
      (node (ref "USB") (pin "P2") (pinfunction "D-_P2") (pintype "bidirectional"))
    )
    (net (code "50") (name "TARGET_USB_P") (class "Default")
      (node (ref "IC1") (pin "34") (pinfunction "PA25/EIC/SCOM3PAD3+/TC5_34") (pintype "bidirectional"))
      (node (ref "USB") (pin "P3") (pinfunction "D+_P3") (pintype "bidirectional"))
    )
    (net (code "51") (name "TXD") (class "Default")
      (node (ref "IC1") (pin "37") (pinfunction "PB22/EIC/SCOM5PAD2_37") (pintype "bidirectional"))
    )
    (net (code "52") (name "VBUS") (class "Default")
      (node (ref "C6") (pin "1") (pinfunction "1_1") (pintype "passive"))
      (node (ref "IC3") (pin "8") (pinfunction "IN1_8") (pintype "bidirectional"))
      (node (ref "IC4") (pin "1") (pinfunction "OUT_1") (pintype "power_in"))
      (node (ref "JP2") (pin "12") (pinfunction "12_12") (pintype "passive"))
      (node (ref "R3") (pin "1") (pinfunction "1_1") (pintype "passive"))
      (node (ref "USB") (pin "P1") (pinfunction "VBUS_P1") (pintype "power_in"))
    )
    (net (code "53") (name "VIN") (class "Default")
      (node (ref "IC3") (pin "6") (pinfunction "IN2_6") (pintype "bidirectional"))
      (node (ref "IC4") (pin "3") (pinfunction "IN_3") (pintype "power_in"))
      (node (ref "JP2") (pin "14") (pinfunction "14_14") (pintype "passive"))
    )
    (net (code "54") (name "VOUT") (class "Default")
      (node (ref "C9") (pin "1") (pinfunction "1_1") (pintype "passive"))
      (node (ref "IC2") (pin "1") (pinfunction "IN_1") (pintype "input"))
      (node (ref "IC2") (pin "3") (pinfunction "EN_3") (pintype "input"))
      (node (ref "IC3") (pin "7") (pinfunction "OUT_7") (pintype "bidirectional"))
      (node (ref "JP2") (pin "11") (pinfunction "11_11") (pintype "passive"))
    )
    (net (code "55") (name "unconnected-(IC2-ADJ-Pad4)") (class "Default")
      (node (ref "IC2") (pin "4") (pinfunction "ADJ_4") (pintype "input"))
    )
    (net (code "56") (name "unconnected-(IC3-STAT-Pad1)") (class "Default")
      (node (ref "IC3") (pin "1") (pinfunction "STAT_1") (pintype "bidirectional"))
    )
    (net (code "57") (name "unconnected-(JP4-Pad6)") (class "Default")
      (node (ref "JP4") (pin "6") (pinfunction "6_6") (pintype "passive"))
    )
    (net (code "58") (name "unconnected-(JP4-Pad7)") (class "Default")
      (node (ref "JP4") (pin "7") (pinfunction "7_7") (pintype "passive"))
    )
    (net (code "59") (name "unconnected-(JP4-Pad8)") (class "Default")
      (node (ref "JP4") (pin "8") (pinfunction "8_8") (pintype "passive"))
    )
    (net (code "60") (name "unconnected-(TP_5V-TESTP-PadX)") (class "Default")
      (node (ref "TP_5V") (pin "X") (pinfunction "TESTP_X") (pintype "passive"))
    )
  )
)
